# 1_P1.net
KiCad netlist of a schematic drawn in Altium Designer
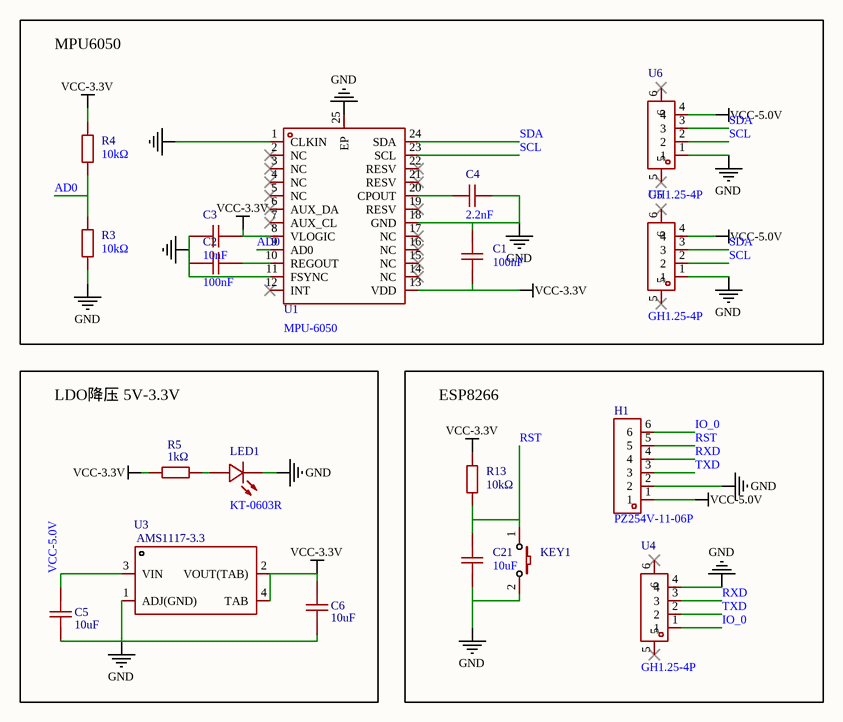
[diagram p0: 1_P1.schdoc]

(export (version "E")
  (design (tool "Eeschema 10.0.6"))
  (components
    (comp (ref "C1")
      (value "100nF")
      (footprint "C0603")
      (fields
        (field (name "MANUFACTURER") "HRE(芯声)")
        (field (name "MANUFACTURER PART") "CGA0603X7R104K500JT")
        (field (name "TOLERANCE") "±10%")
      )
      (libsource (lib "altium-import") (part "root_1_mirrored_CGA0603X7R104K500JT_"))
    )
    (comp (ref "C2")
      (value "100nF")
      (footprint "C0603")
      (fields
        (field (name "MANUFACTURER") "HRE(芯声)")
        (field (name "MANUFACTURER PART") "CGA0603X7R104K500JT")
        (field (name "TOLERANCE") "±10%")
      )
      (libsource (lib "altium-import") (part "root_2_CGA0603X7R104K500JT_"))
    )
    (comp (ref "C3")
      (value "10nF")
      (footprint "C0603")
      (fields
        (field (name "MANUFACTURER") "YAGEO(国巨)")
        (field (name "MANUFACTURER PART") "CC0603KRX7R9BB103")
        (field (name "TOLERANCE") "±10%")
      )
      (libsource (lib "altium-import") (part "root_0_CC0603KRX7R9BB103_"))
    )
    (comp (ref "C4")
      (value "2.2nF")
      (footprint "C0603")
      (fields
        (field (name "MANUFACTURER") "YAGEO(国巨)")
        (field (name "MANUFACTURER PART") "CC0603KRX7R9BB222")
        (field (name "TOLERANCE") "±10%")
      )
      (libsource (lib "altium-import") (part "root_0_CC0603KRX7R9BB222_"))
    )
    (comp (ref "C5")
      (value "10uF")
      (footprint "C0603")
      (fields
        (field (name "MANUFACTURER") "HRE(芯声)")
        (field (name "MANUFACTURER PART") "CGA0603X5R106K100JT")
        (field (name "TOLERANCE") "±10%")
      )
      (libsource (lib "altium-import") (part "root_1_CGA0603X5R106K100JT_"))
    )
    (comp (ref "C6")
      (value "10uF")
      (footprint "C0603")
      (fields
        (field (name "MANUFACTURER") "HRE(芯声)")
        (field (name "MANUFACTURER PART") "CGA0603X5R106K100JT")
        (field (name "TOLERANCE") "±10%")
      )
      (libsource (lib "altium-import") (part "root_1_CGA0603X5R106K100JT_"))
    )
    (comp (ref "C21")
      (value "10uF")
      (footprint "C0603")
      (fields
        (field (name "MANUFACTURER") "HRE(芯声)")
        (field (name "MANUFACTURER PART") "CGA0603X5R106K100JT")
        (field (name "TOLERANCE") "±10%")
      )
      (libsource (lib "altium-import") (part "root_3_CGA0603X5R106K100JT_"))
    )
    (comp (ref "H1")
      (value "PZ254V-11-06P")
      (footprint "HDR-TH_6P-P2.54-V-M")
      (fields (field (name "MANUFACTURER") "XFCN(兴飞)"))
      (libsource (lib "altium-import") (part "root_2_PZ254V-11-06P_"))
    )
    (comp (ref "KEY1")
      (value "K2-3.6×6.1_SMD")
      (footprint "KEY-SMD_2P-L6.2-W3.6-LS8.0")
      (fields (field (name "MANUFACTURER PART") "K2-1107ST-A4SW-06"))
      (libsource (lib "altium-import") (part "root_3_K2-3.6×6.1_SMD_"))
    )
    (comp (ref "LED1")
      (value "KT-0603R")
      (footprint "LED0603-RD")
      (fields (field (name "MANUFACTURER") "KENTO"))
      (libsource (lib "altium-import") (part "root_2_KT-0603R_"))
    )
    (comp (ref "R3")
      (value "10kΩ")
      (footprint "R0603")
      (fields
        (field (name "MANUFACTURER") "UNI-ROYAL(厚声)")
        (field (name "MANUFACTURER PART") "0603WAF1002T5E")
        (field (name "TOLERANCE") "±1%")
      )
      (libsource (lib "altium-import") (part "root_1_0603WAF1002T5E_"))
    )
    (comp (ref "R4")
      (value "10kΩ")
      (footprint "R0603")
      (fields
        (field (name "MANUFACTURER") "UNI-ROYAL(厚声)")
        (field (name "MANUFACTURER PART") "0603WAF1002T5E")
        (field (name "TOLERANCE") "±1%")
      )
      (libsource (lib "altium-import") (part "root_1_0603WAF1002T5E_"))
    )
    (comp (ref "R5")
      (value "1kΩ")
      (footprint "R0603")
      (fields
        (field (name "MANUFACTURER") "UNI-ROYAL(厚声)")
        (field (name "MANUFACTURER PART") "0603WAF1001T5E")
        (field (name "TOLERANCE") "±1%")
      )
      (libsource (lib "altium-import") (part "root_0_0603WAF1001T5E_"))
    )
    (comp (ref "R13")
      (value "10kΩ")
      (footprint "R0603")
      (fields
        (field (name "MANUFACTURER") "UNI-ROYAL(厚声)")
        (field (name "MANUFACTURER PART") "0603WAF1002T5E")
        (field (name "TOLERANCE") "±1%")
      )
      (libsource (lib "altium-import") (part "root_1_0603WAF1002T5E_"))
    )
    (comp (ref "U1")
      (value "MPU-6050")
      (footprint "QFN-24_L4.0-W4.0-P0.50-BL-EP2.7")
      (fields (field (name "MANUFACTURER") "TDK InvenSense(应美盛)"))
      (libsource (lib "altium-import") (part "root_0_MPU-6050_"))
    )
    (comp (ref "U3")
      (value "AMS1117-3.3")
      (footprint "SOT-223_L6.7-W3.5-P2.30-BR")
      (fields (field (name "MANUFACTURER") "Youtai Semiconductor Co., Ltd."))
      (libsource (lib "altium-import") (part "root_0_AMS1117-3.3_"))
    )
    (comp (ref "U4")
      (value "GH1.25-4P")
      (footprint "CONN-SMD_GH1.25-4P")
      (libsource (lib "altium-import") (part "root_2_GH1.25-4P_C9900006327_"))
    )
    (comp (ref "U5")
      (value "GH1.25-4P")
      (footprint "CONN-SMD_GH1.25-4P")
      (libsource (lib "altium-import") (part "root_2_GH1.25-4P_C9900006327_"))
    )
    (comp (ref "U6")
      (value "GH1.25-4P")
      (footprint "CONN-SMD_GH1.25-4P")
      (libsource (lib "altium-import") (part "root_2_GH1.25-4P_C9900006327_"))
    )
  )
  (nets
    (net (code "1") (name "/AD0") (class "Default")
      (node (ref "R3") (pin "2") (pinfunction "2_2") (pintype "passive"))
      (node (ref "R4") (pin "1") (pinfunction "1_1") (pintype "passive"))
      (node (ref "U1") (pin "9") (pinfunction "AD0_9") (pintype "passive"))
    )
    (net (code "2") (name "/IO_0") (class "Default")
      (node (ref "H1") (pin "6") (pinfunction "6_6") (pintype "passive"))
      (node (ref "U4") (pin "1") (pinfunction "1_1") (pintype "passive"))
    )
    (net (code "3") (name "/RST") (class "Default")
      (node (ref "C21") (pin "1") (pinfunction "1_1") (pintype "passive"))
      (node (ref "H1") (pin "5") (pinfunction "5_5") (pintype "passive"))
      (node (ref "KEY1") (pin "1") (pinfunction "1_1") (pintype "passive"))
      (node (ref "R13") (pin "1") (pinfunction "1_1") (pintype "passive"))
    )
    (net (code "4") (name "/RXD") (class "Default")
      (node (ref "H1") (pin "4") (pinfunction "4_4") (pintype "passive"))
      (node (ref "U4") (pin "3") (pinfunction "3_3") (pintype "passive"))
    )
    (net (code "5") (name "/SCL") (class "Default")
      (node (ref "U1") (pin "23") (pinfunction "SCL_23") (pintype "passive"))
      (node (ref "U5") (pin "2") (pinfunction "2_2") (pintype "passive"))
      (node (ref "U6") (pin "2") (pinfunction "2_2") (pintype "passive"))
    )
    (net (code "6") (name "/SDA") (class "Default")
      (node (ref "U1") (pin "24") (pinfunction "SDA_24") (pintype "passive"))
      (node (ref "U5") (pin "3") (pinfunction "3_3") (pintype "passive"))
      (node (ref "U6") (pin "3") (pinfunction "3_3") (pintype "passive"))
    )
    (net (code "7") (name "/TXD") (class "Default")
      (node (ref "H1") (pin "3") (pinfunction "3_3") (pintype "passive"))
      (node (ref "U4") (pin "2") (pinfunction "2_2") (pintype "passive"))
    )
    (net (code "8") (name "GND") (class "Default")
      (node (ref "C1") (pin "2") (pinfunction "2_2") (pintype "passive"))
      (node (ref "C2") (pin "2") (pinfunction "2_2") (pintype "passive"))
      (node (ref "C21") (pin "2") (pinfunction "2_2") (pintype "passive"))
      (node (ref "C3") (pin "1") (pinfunction "1_1") (pintype "passive"))
      (node (ref "C4") (pin "2") (pinfunction "2_2") (pintype "passive"))
      (node (ref "C5") (pin "1") (pinfunction "1_1") (pintype "passive"))
      (node (ref "C6") (pin "1") (pinfunction "1_1") (pintype "passive"))
      (node (ref "H1") (pin "2") (pinfunction "2_2") (pintype "passive"))
      (node (ref "KEY1") (pin "2") (pinfunction "2_2") (pintype "passive"))
      (node (ref "LED1") (pin "1") (pinfunction "K_1") (pintype "passive"))
      (node (ref "R3") (pin "1") (pinfunction "1_1") (pintype "passive"))
      (node (ref "U1") (pin "1") (pinfunction "CLKIN_1") (pintype "passive"))
      (node (ref "U1") (pin "11") (pinfunction "FSYNC_11") (pintype "passive"))
      (node (ref "U1") (pin "18") (pinfunction "GND_18") (pintype "passive"))
      (node (ref "U1") (pin "25") (pinfunction "EP_25") (pintype "passive"))
      (node (ref "U3") (pin "1") (pinfunction "ADJ(GND)_1") (pintype "passive"))
      (node (ref "U4") (pin "4") (pinfunction "4_4") (pintype "passive"))
      (node (ref "U5") (pin "1") (pinfunction "1_1") (pintype "passive"))
      (node (ref "U6") (pin "1") (pinfunction "1_1") (pintype "passive"))
    )
    (net (code "9") (name "Net-(LED1-A)") (class "Default")
      (node (ref "LED1") (pin "2") (pinfunction "A_2") (pintype "passive"))
      (node (ref "R5") (pin "2") (pinfunction "2_2") (pintype "passive"))
    )
    (net (code "10") (name "Net-(U1-CPOUT)") (class "Default")
      (node (ref "C4") (pin "1") (pinfunction "1_1") (pintype "passive"))
      (node (ref "U1") (pin "20") (pinfunction "CPOUT_20") (pintype "passive"))
    )
    (net (code "11") (name "Net-(U1-REGOUT)") (class "Default")
      (node (ref "C2") (pin "1") (pinfunction "1_1") (pintype "passive"))
      (node (ref "U1") (pin "10") (pinfunction "REGOUT_10") (pintype "passive"))
    )
    (net (code "12") (name "VCC-3.3V") (class "Default")
      (node (ref "C1") (pin "1") (pinfunction "1_1") (pintype "passive"))
      (node (ref "C3") (pin "2") (pinfunction "2_2") (pintype "passive"))
      (node (ref "C6") (pin "2") (pinfunction "2_2") (pintype "passive"))
      (node (ref "R13") (pin "2") (pinfunction "2_2") (pintype "passive"))
      (node (ref "R4") (pin "2") (pinfunction "2_2") (pintype "passive"))
      (node (ref "R5") (pin "1") (pinfunction "1_1") (pintype "passive"))
      (node (ref "U1") (pin "13") (pinfunction "VDD_13") (pintype "passive"))
      (node (ref "U1") (pin "8") (pinfunction "VLOGIC_8") (pintype "passive"))
      (node (ref "U3") (pin "2") (pinfunction "VOUT(TAB)_2") (pintype "passive"))
      (node (ref "U3") (pin "4") (pinfunction "TAB_4") (pintype "passive"))
    )
    (net (code "13") (name "VCC-5.0V") (class "Default")
      (node (ref "C5") (pin "2") (pinfunction "2_2") (pintype "passive"))
      (node (ref "H1") (pin "1") (pinfunction "1_1") (pintype "passive"))
      (node (ref "U3") (pin "3") (pinfunction "VIN_3") (pintype "passive"))
      (node (ref "U5") (pin "4") (pinfunction "4_4") (pintype "passive"))
      (node (ref "U6") (pin "4") (pinfunction "4_4") (pintype "passive"))
    )
    (net (code "14") (name "unconnected-(U1-AUX_CL-Pad7)") (class "Default")
      (node (ref "U1") (pin "7") (pinfunction "AUX_CL_7") (pintype "passive+no_connect"))
    )
    (net (code "15") (name "unconnected-(U1-AUX_DA-Pad6)") (class "Default")
      (node (ref "U1") (pin "6") (pinfunction "AUX_DA_6") (pintype "passive+no_connect"))
    )
    (net (code "16") (name "unconnected-(U1-INT-Pad12)") (class "Default")
      (node (ref "U1") (pin "12") (pinfunction "INT_12") (pintype "passive+no_connect"))
    )
    (net (code "17") (name "unconnected-(U1-NC-Pad2)") (class "Default")
      (node (ref "U1") (pin "2") (pinfunction "NC_2") (pintype "passive+no_connect"))
    )
    (net (code "18") (name "unconnected-(U1-NC-Pad3)") (class "Default")
      (node (ref "U1") (pin "3") (pinfunction "NC_3") (pintype "passive+no_connect"))
    )
    (net (code "19") (name "unconnected-(U1-NC-Pad4)") (class "Default")
      (node (ref "U1") (pin "4") (pinfunction "NC_4") (pintype "passive+no_connect"))
    )
    (net (code "20") (name "unconnected-(U1-NC-Pad5)") (class "Default")
      (node (ref "U1") (pin "5") (pinfunction "NC_5") (pintype "passive+no_connect"))
    )
    (net (code "21") (name "unconnected-(U1-NC-Pad14)") (class "Default")
      (node (ref "U1") (pin "14") (pinfunction "NC_14") (pintype "passive+no_connect"))
    )
    (net (code "22") (name "unconnected-(U1-NC-Pad15)") (class "Default")
      (node (ref "U1") (pin "15") (pinfunction "NC_15") (pintype "passive+no_connect"))
    )
    (net (code "23") (name "unconnected-(U1-NC-Pad16)") (class "Default")
      (node (ref "U1") (pin "16") (pinfunction "NC_16") (pintype "passive+no_connect"))
    )
    (net (code "24") (name "unconnected-(U1-NC-Pad17)") (class "Default")
      (node (ref "U1") (pin "17") (pinfunction "NC_17") (pintype "passive+no_connect"))
    )
    (net (code "25") (name "unconnected-(U1-RESV-Pad19)") (class "Default")
      (node (ref "U1") (pin "19") (pinfunction "RESV_19") (pintype "passive+no_connect"))
    )
    (net (code "26") (name "unconnected-(U1-RESV-Pad21)") (class "Default")
      (node (ref "U1") (pin "21") (pinfunction "RESV_21") (pintype "passive+no_connect"))
    )
    (net (code "27") (name "unconnected-(U1-RESV-Pad22)") (class "Default")
      (node (ref "U1") (pin "22") (pinfunction "RESV_22") (pintype "passive+no_connect"))
    )
    (net (code "28") (name "unconnected-(U4-Pad5)") (class "Default")
      (node (ref "U4") (pin "5") (pinfunction "5_5") (pintype "passive+no_connect"))
    )
    (net (code "29") (name "unconnected-(U4-Pad6)") (class "Default")
      (node (ref "U4") (pin "6") (pinfunction "6_6") (pintype "passive+no_connect"))
    )
    (net (code "30") (name "unconnected-(U5-Pad5)") (class "Default")
      (node (ref "U5") (pin "5") (pinfunction "5_5") (pintype "passive+no_connect"))
    )
    (net (code "31") (name "unconnected-(U5-Pad6)") (class "Default")
      (node (ref "U5") (pin "6") (pinfunction "6_6") (pintype "passive+no_connect"))
    )
    (net (code "32") (name "unconnected-(U6-Pad5)") (class "Default")
      (node (ref "U6") (pin "5") (pinfunction "5_5") (pintype "passive+no_connect"))
    )
    (net (code "33") (name "unconnected-(U6-Pad6)") (class "Default")
      (node (ref "U6") (pin "6") (pinfunction "6_6") (pintype "passive+no_connect"))
    )
  )
)
